# io_board.net
KiCad netlist of a schematic drawn in EAGLE
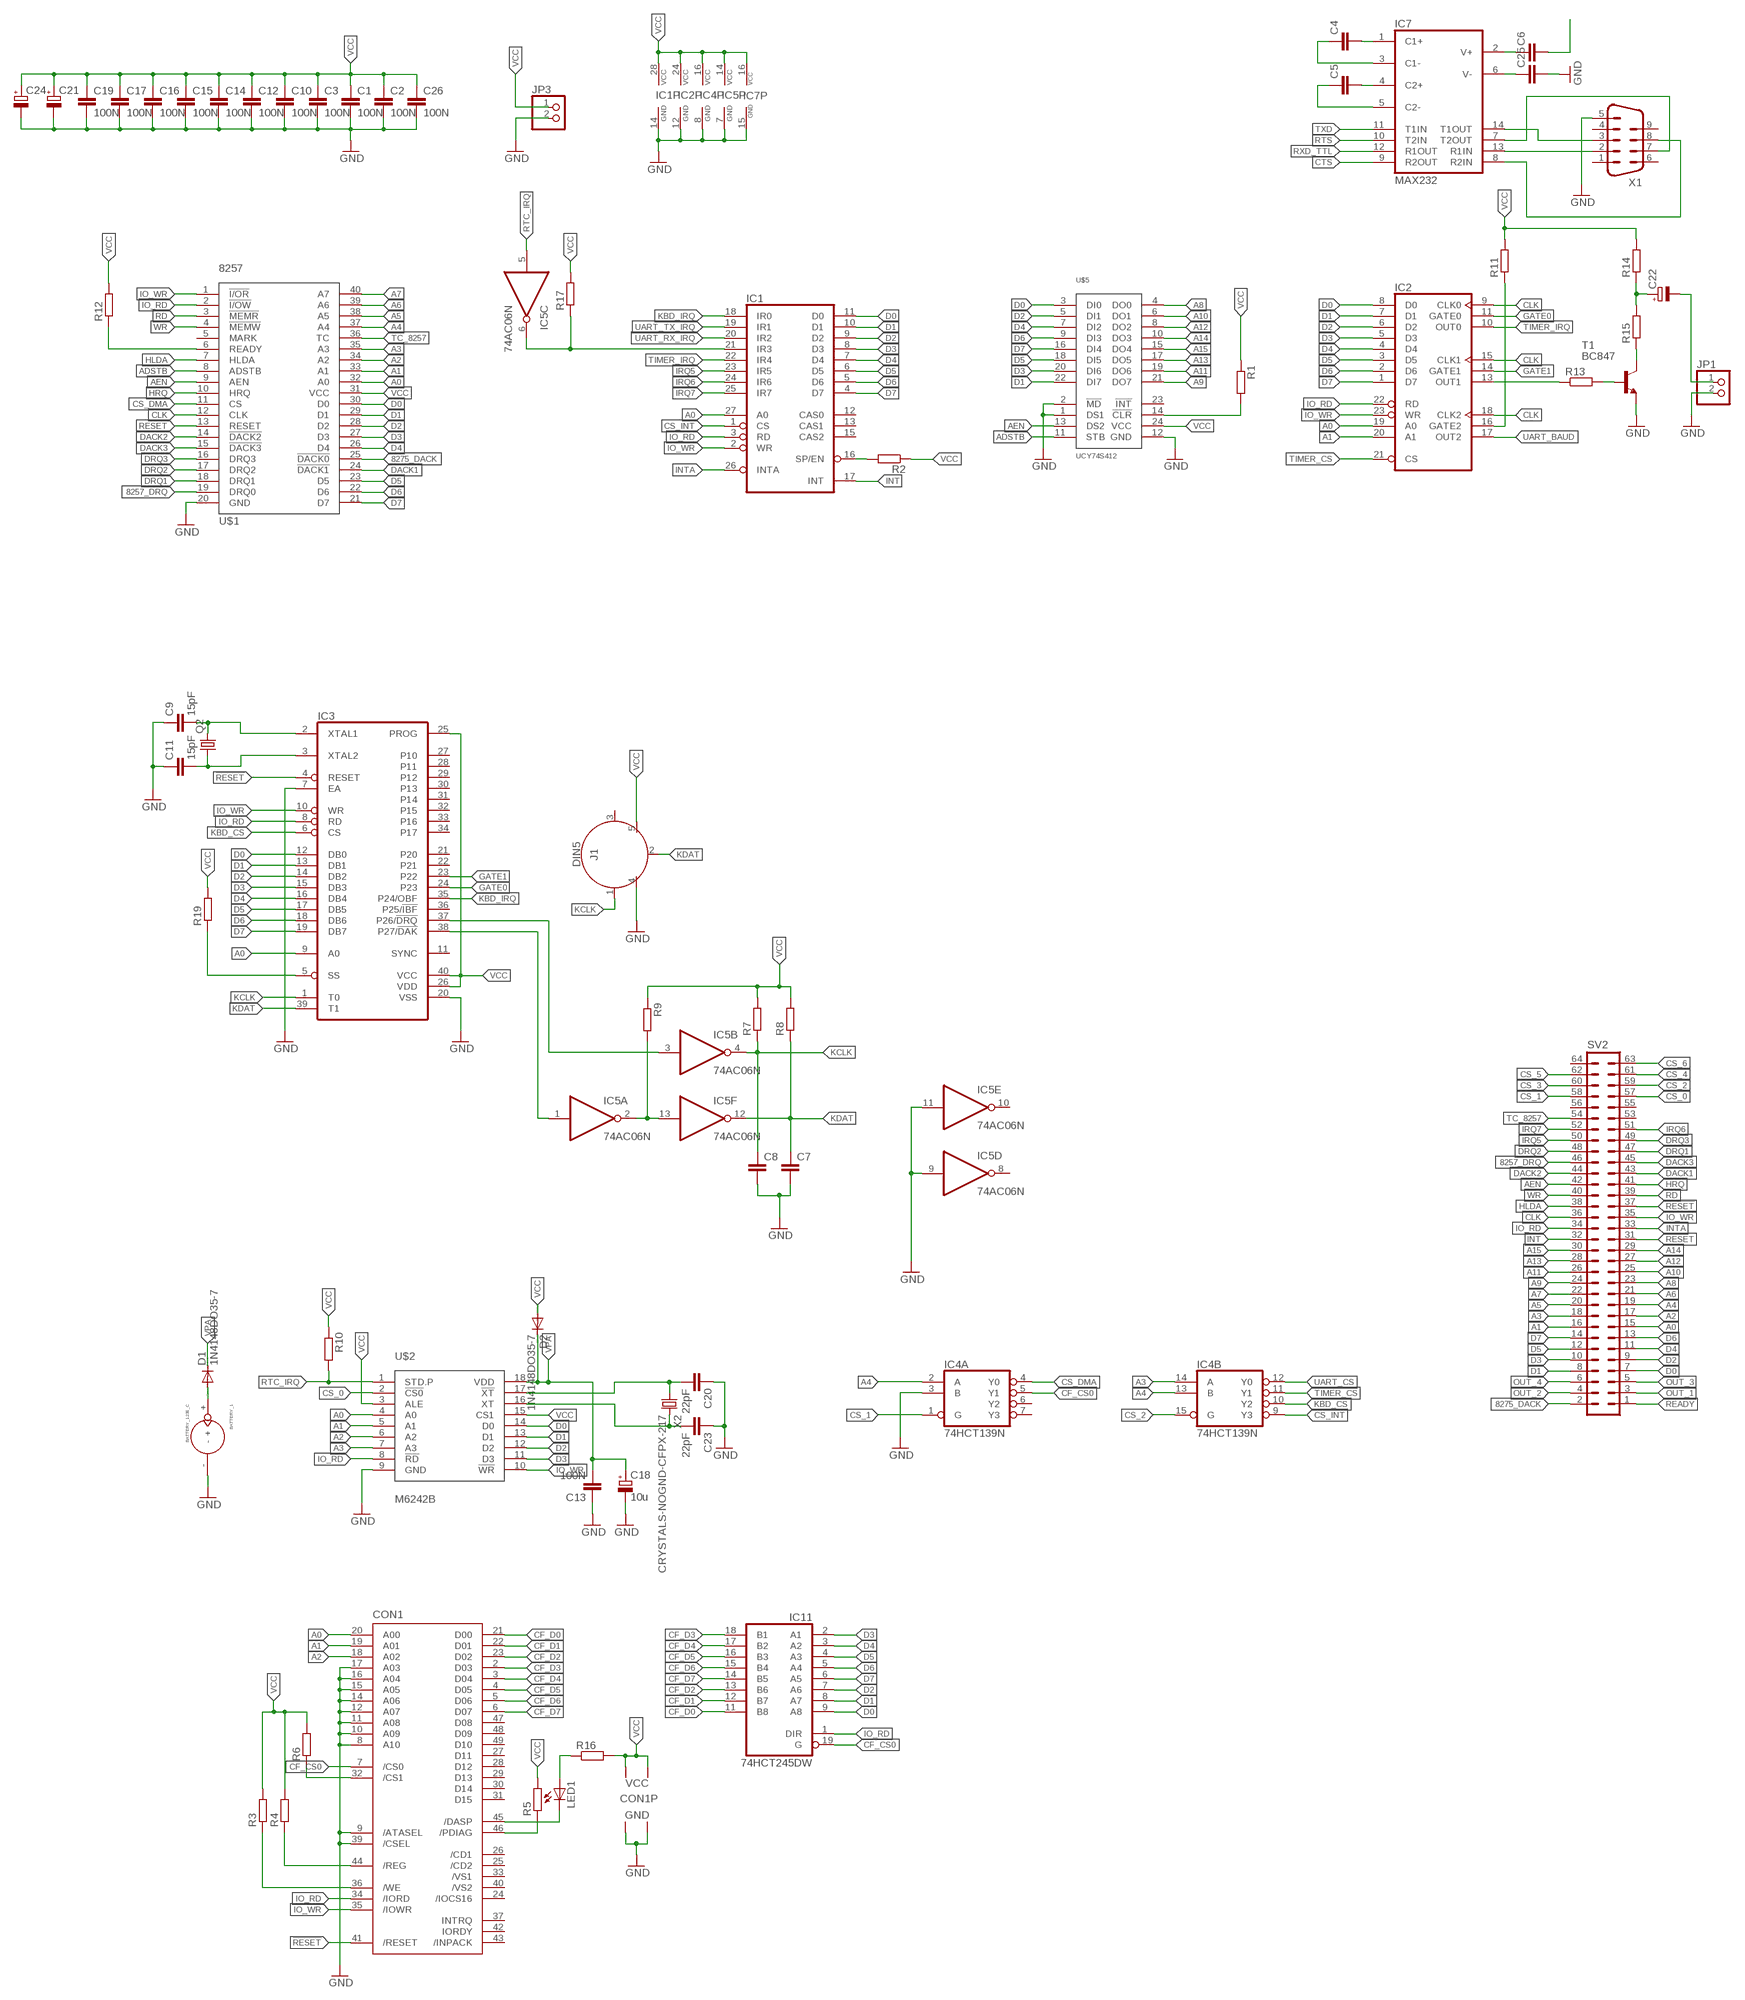
[diagram p0: schematic, sheet 1, part 1 of 2]
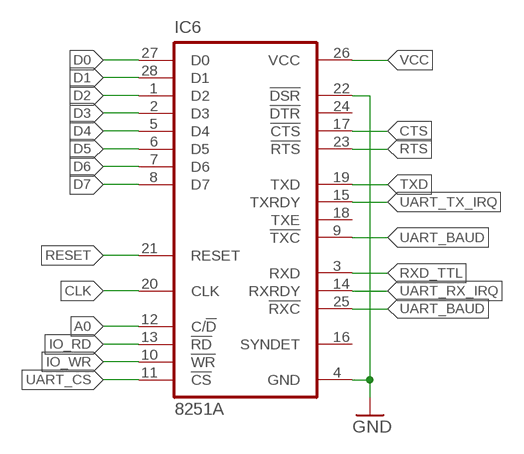
[diagram p1: schematic, sheet 1, part 2 of 2]

(export (version "E")
  (design (tool "Eeschema 10.0.6"))
  (components
    (comp (ref "BATTERY_1")
      (value "BATTERY_1236_C")
      (footprint "eagle-import:BATTERY_1236_C")
      (libsource (lib "eagle-import") (part "BATTERY_1236_C"))
    )
    (comp (ref "C1")
      (value "100N")
      (footprint "eagle-import:C0603")
      (libsource (lib "eagle-import") (part "C-EUC0603"))
    )
    (comp (ref "C2")
      (value "100N")
      (footprint "eagle-import:C1206")
      (libsource (lib "eagle-import") (part "C-EUC1206"))
    )
    (comp (ref "C3")
      (value "100N")
      (footprint "eagle-import:C0603")
      (libsource (lib "eagle-import") (part "C-EUC0603"))
    )
    (comp (ref "C4")
      (value "C-EUC0603")
      (footprint "eagle-import:C0603")
      (libsource (lib "eagle-import") (part "C-EUC0603"))
    )
    (comp (ref "C5")
      (value "C-EUC0603")
      (footprint "eagle-import:C0603")
      (libsource (lib "eagle-import") (part "C-EUC0603"))
    )
    (comp (ref "C6")
      (value "C-EUC0603")
      (footprint "eagle-import:C0603")
      (libsource (lib "eagle-import") (part "C-EUC0603"))
    )
    (comp (ref "C7")
      (value "C-EUC0603")
      (footprint "eagle-import:C0603")
      (libsource (lib "eagle-import") (part "C-EUC0603"))
    )
    (comp (ref "C8")
      (value "C-EUC0603")
      (footprint "eagle-import:C0603")
      (libsource (lib "eagle-import") (part "C-EUC0603"))
    )
    (comp (ref "C9")
      (value "15pF")
      (footprint "eagle-import:C0603")
      (libsource (lib "eagle-import") (part "C-EUC0603"))
    )
    (comp (ref "C10")
      (value "100N")
      (footprint "eagle-import:C0603")
      (libsource (lib "eagle-import") (part "C-EUC0603"))
    )
    (comp (ref "C11")
      (value "15pF")
      (footprint "eagle-import:C0603")
      (libsource (lib "eagle-import") (part "C-EUC0603"))
    )
    (comp (ref "C12")
      (value "100N")
      (footprint "eagle-import:C0603")
      (libsource (lib "eagle-import") (part "C-EUC0603"))
    )
    (comp (ref "C13")
      (value "100N")
      (footprint "eagle-import:C0603")
      (libsource (lib "eagle-import") (part "C-EUC0603"))
    )
    (comp (ref "C14")
      (value "100N")
      (footprint "eagle-import:C0603")
      (libsource (lib "eagle-import") (part "C-EUC0603"))
    )
    (comp (ref "C15")
      (value "100N")
      (footprint "eagle-import:C0603")
      (libsource (lib "eagle-import") (part "C-EUC0603"))
    )
    (comp (ref "C16")
      (value "100N")
      (footprint "eagle-import:C0603")
      (libsource (lib "eagle-import") (part "C-EUC0603"))
    )
    (comp (ref "C17")
      (value "100N")
      (footprint "eagle-import:C0603")
      (libsource (lib "eagle-import") (part "C-EUC0603"))
    )
    (comp (ref "C18")
      (value "10u")
      (footprint "eagle-import:SMC_B")
      (libsource (lib "eagle-import") (part "CPOL-EUSMCB"))
    )
    (comp (ref "C19")
      (value "100N")
      (footprint "eagle-import:C0603")
      (libsource (lib "eagle-import") (part "C-EUC0603"))
    )
    (comp (ref "C20")
      (value "22pF")
      (footprint "eagle-import:C0603")
      (libsource (lib "eagle-import") (part "C-EUC0603"))
    )
    (comp (ref "C21")
      (value "CPOL-EUE3.5-8")
      (footprint "eagle-import:E3,5-8")
      (libsource (lib "eagle-import") (part "CPOL-EUE3.5-8"))
    )
    (comp (ref "C22")
      (value "CPOL-EUE2-4")
      (footprint "eagle-import:E2-4")
      (libsource (lib "eagle-import") (part "CPOL-EUE2-4"))
    )
    (comp (ref "C23")
      (value "22pF")
      (footprint "eagle-import:C0603")
      (libsource (lib "eagle-import") (part "C-EUC0603"))
    )
    (comp (ref "C24")
      (value "CPOL-EUSMCB")
      (footprint "eagle-import:SMC_B")
      (libsource (lib "eagle-import") (part "CPOL-EUSMCB"))
    )
    (comp (ref "C25")
      (value "C-EUC0603")
      (footprint "eagle-import:C0603")
      (libsource (lib "eagle-import") (part "C-EUC0603"))
    )
    (comp (ref "C26")
      (value "100N")
      (footprint "eagle-import:C0603")
      (libsource (lib "eagle-import") (part "C-EUC0603"))
    )
    (comp (ref "CON1")
      (value "CF-CARD-IDE_MODE")
      (footprint "eagle-import:MI20-50PD-SF")
      (libsource (lib "eagle-import") (part "CF-CARD-IDE_MODE"))
    )
    (comp (ref "D1")
      (value "1N4148DO35-7")
      (footprint "eagle-import:DO35-7")
      (libsource (lib "eagle-import") (part "1N4148DO35-7"))
    )
    (comp (ref "D2")
      (value "1N4148DO35-7")
      (footprint "eagle-import:DO35-7")
      (libsource (lib "eagle-import") (part "1N4148DO35-7"))
    )
    (comp (ref "IC1")
      (value "8259A")
      (footprint "eagle-import:DIL28-6")
      (libsource (lib "eagle-import") (part "8259A"))
    )
    (comp (ref "IC2")
      (value "8253")
      (footprint "eagle-import:DIL24-6")
      (libsource (lib "eagle-import") (part "8253"))
    )
    (comp (ref "IC3")
      (value "UPI-8042AH")
      (footprint "eagle-import:DIL40")
      (libsource (lib "eagle-import") (part "UPI-8042AH"))
    )
    (comp (ref "IC4")
      (value "74HCT139N")
      (footprint "eagle-import:DIL16")
      (libsource (lib "eagle-import") (part "74139NHCT"))
    )
    (comp (ref "IC5")
      (value "74AC06N")
      (footprint "eagle-import:DIL14")
      (libsource (lib "eagle-import") (part "7406NAC"))
    )
    (comp (ref "IC6")
      (value "8251A")
      (footprint "eagle-import:DIL28-6")
      (libsource (lib "eagle-import") (part "8251A"))
    )
    (comp (ref "IC7")
      (value "MAX232")
      (footprint "eagle-import:DIL16")
      (fields (field (name "MF") "MAXIM") (field (name "MPN") "MAX232ACPE+"))
      (libsource (lib "eagle-import") (part "MAX232"))
    )
    (comp (ref "IC11")
      (value "74HCT245DW")
      (footprint "eagle-import:SO20W")
      (libsource (lib "eagle-import") (part "74245DWHCT"))
    )
    (comp (ref "J1")
      (value "DIN5")
      (footprint "eagle-import:DIN5-RA-PTH")
      (libsource (lib "eagle-import") (part "DIN5"))
    )
    (comp (ref "JP1")
      (value "PINHD-1X2")
      (footprint "eagle-import:1X02")
      (libsource (lib "eagle-import") (part "PINHD-1X2"))
    )
    (comp (ref "JP3")
      (value "PINHD-1X2/90")
      (footprint "eagle-import:1X02_90")
      (libsource (lib "eagle-import") (part "PINHD-1X2/90"))
    )
    (comp (ref "LED1")
      (value "LED5MM")
      (footprint "eagle-import:LED5MM")
      (libsource (lib "eagle-import") (part "LED5MM"))
    )
    (comp (ref "Q2")
      (value "CRYSTALHC49S")
      (footprint "eagle-import:HC49_S")
      (libsource (lib "eagle-import") (part "CRYSTALHC49S"))
    )
    (comp (ref "R1")
      (value "R-EU_R0603")
      (footprint "eagle-import:R0603")
      (libsource (lib "eagle-import") (part "R-EU_R0603"))
    )
    (comp (ref "R2")
      (value "R-EU_R0603")
      (footprint "eagle-import:R0603")
      (libsource (lib "eagle-import") (part "R-EU_R0603"))
    )
    (comp (ref "R3")
      (value "R-EU_R0603")
      (footprint "eagle-import:R0603")
      (libsource (lib "eagle-import") (part "R-EU_R0603"))
    )
    (comp (ref "R4")
      (value "R-EU_0204/7")
      (footprint "eagle-import:0204_7")
      (libsource (lib "eagle-import") (part "R-EU_0204/7"))
    )
    (comp (ref "R5")
      (value "R-EU_0207/10")
      (footprint "eagle-import:0207_10")
      (libsource (lib "eagle-import") (part "R-EU_0207/10"))
    )
    (comp (ref "R6")
      (value "R-EU_R0603")
      (footprint "eagle-import:R0603")
      (libsource (lib "eagle-import") (part "R-EU_R0603"))
    )
    (comp (ref "R7")
      (value "R-EU_0204/5")
      (footprint "eagle-import:0204_5")
      (libsource (lib "eagle-import") (part "R-EU_0204/5"))
    )
    (comp (ref "R8")
      (value "R-EU_M0805")
      (footprint "eagle-import:M0805")
      (libsource (lib "eagle-import") (part "R-EU_M0805"))
    )
    (comp (ref "R9")
      (value "R-EU_R0603")
      (footprint "eagle-import:R0603")
      (libsource (lib "eagle-import") (part "R-EU_R0603"))
    )
    (comp (ref "R10")
      (value "R-EU_R0603")
      (footprint "eagle-import:R0603")
      (libsource (lib "eagle-import") (part "R-EU_R0603"))
    )
    (comp (ref "R11")
      (value "R-EU_R0603")
      (footprint "eagle-import:R0603")
      (libsource (lib "eagle-import") (part "R-EU_R0603"))
    )
    (comp (ref "R12")
      (value "R-EU_R0603")
      (footprint "eagle-import:R0603")
      (libsource (lib "eagle-import") (part "R-EU_R0603"))
    )
    (comp (ref "R13")
      (value "R-EU_R0603")
      (footprint "eagle-import:R0603")
      (libsource (lib "eagle-import") (part "R-EU_R0603"))
    )
    (comp (ref "R14")
      (value "R-EU_0204/5")
      (footprint "eagle-import:0204_5")
      (libsource (lib "eagle-import") (part "R-EU_0204/5"))
    )
    (comp (ref "R15")
      (value "R-EU_R0603")
      (footprint "eagle-import:R0603")
      (libsource (lib "eagle-import") (part "R-EU_R0603"))
    )
    (comp (ref "R16")
      (value "R-EU_R0603")
      (footprint "eagle-import:R0603")
      (libsource (lib "eagle-import") (part "R-EU_R0603"))
    )
    (comp (ref "R17")
      (value "R-EU_0204/7")
      (footprint "eagle-import:0204_7")
      (libsource (lib "eagle-import") (part "R-EU_0204/7"))
    )
    (comp (ref "R19")
      (value "R-EU_0204/5")
      (footprint "eagle-import:0204_5")
      (libsource (lib "eagle-import") (part "R-EU_0204/5"))
    )
    (comp (ref "SV2")
      (value "ML64L")
      (footprint "eagle-import:ML64L")
      (libsource (lib "eagle-import") (part "ML64L"))
    )
    (comp (ref "T1")
      (value "BC847")
      (footprint "eagle-import:SOT23")
      (libsource (lib "eagle-import") (part "BC847"))
    )
    (comp (ref "U$1")
      (value "8257")
      (footprint "eagle-import:DIL40")
      (libsource (lib "eagle-import") (part "8257"))
    )
    (comp (ref "U$2")
      (value "M6242B")
      (footprint "eagle-import:DIL18")
      (libsource (lib "eagle-import") (part "M6242B"))
    )
    (comp (ref "U$5")
      (value "UCY74S412")
      (footprint "eagle-import:DIL24-6")
      (libsource (lib "eagle-import") (part "UCY74S412"))
    )
    (comp (ref "X1")
      (value "M09HP")
      (footprint "eagle-import:M09HP")
      (libsource (lib "eagle-import") (part "M09HP"))
    )
    (comp (ref "X2")
      (value "CRYSTALS-NOGND-CFPX-217")
      (footprint "eagle-import:3.2X1.5-2-PAD")
      (libsource (lib "eagle-import") (part "CRYSTALS-NOGND-CFPX-217"))
    )
  )
  (nets
    (net (code "1") (name "/~{RESET}") (class "Default")
      (node (ref "CON1") (pin "41") (pinfunction "/RESET_41") (pintype "input"))
      (node (ref "IC3") (pin "4") (pinfunction "RESET_4") (pintype "input"))
      (node (ref "SV2") (pin "37") (pinfunction "37_37") (pintype "passive"))
    )
    (net (code "2") (name "8257_DRQ") (class "Default")
      (node (ref "SV2") (pin "46") (pinfunction "46_46") (pintype "passive"))
      (node (ref "U$1") (pin "19") (pinfunction "DRQ0_19") (pintype "bidirectional"))
    )
    (net (code "3") (name "8275_DACK") (class "Default")
      (node (ref "SV2") (pin "2") (pinfunction "2_2") (pintype "passive"))
      (node (ref "U$1") (pin "25") (pinfunction "~{DACK0}_25") (pintype "bidirectional"))
    )
    (net (code "4") (name "A0") (class "Default")
      (node (ref "CON1") (pin "20") (pinfunction "A00_20") (pintype "input"))
      (node (ref "IC1") (pin "27") (pinfunction "A0_27") (pintype "input"))
      (node (ref "IC2") (pin "19") (pinfunction "A0_19") (pintype "input"))
      (node (ref "IC3") (pin "9") (pinfunction "A0_9") (pintype "input"))
      (node (ref "IC6") (pin "12") (pinfunction "C/~{D}_12") (pintype "input"))
      (node (ref "SV2") (pin "15") (pinfunction "15_15") (pintype "passive"))
      (node (ref "U$1") (pin "32") (pinfunction "A0_32") (pintype "bidirectional"))
      (node (ref "U$2") (pin "4") (pinfunction "A0_4") (pintype "bidirectional"))
    )
    (net (code "5") (name "A1") (class "Default")
      (node (ref "CON1") (pin "19") (pinfunction "A01_19") (pintype "input"))
      (node (ref "IC2") (pin "20") (pinfunction "A1_20") (pintype "input"))
      (node (ref "SV2") (pin "16") (pinfunction "16_16") (pintype "passive"))
      (node (ref "U$1") (pin "33") (pinfunction "A1_33") (pintype "bidirectional"))
      (node (ref "U$2") (pin "5") (pinfunction "A1_5") (pintype "bidirectional"))
    )
    (net (code "6") (name "A2") (class "Default")
      (node (ref "CON1") (pin "18") (pinfunction "A02_18") (pintype "input"))
      (node (ref "SV2") (pin "17") (pinfunction "17_17") (pintype "passive"))
      (node (ref "U$1") (pin "34") (pinfunction "A2_34") (pintype "bidirectional"))
      (node (ref "U$2") (pin "6") (pinfunction "A2_6") (pintype "bidirectional"))
    )
    (net (code "7") (name "A3") (class "Default")
      (node (ref "IC4") (pin "14") (pinfunction "A_14") (pintype "input"))
      (node (ref "SV2") (pin "18") (pinfunction "18_18") (pintype "passive"))
      (node (ref "U$1") (pin "35") (pinfunction "A3_35") (pintype "bidirectional"))
      (node (ref "U$2") (pin "7") (pinfunction "A3_7") (pintype "bidirectional"))
    )
    (net (code "8") (name "A4") (class "Default")
      (node (ref "IC4") (pin "13") (pinfunction "B_13") (pintype "input"))
      (node (ref "IC4") (pin "2") (pinfunction "A_2") (pintype "input"))
      (node (ref "SV2") (pin "19") (pinfunction "19_19") (pintype "passive"))
      (node (ref "U$1") (pin "37") (pinfunction "A4_37") (pintype "bidirectional"))
    )
    (net (code "9") (name "A5") (class "Default")
      (node (ref "SV2") (pin "20") (pinfunction "20_20") (pintype "passive"))
      (node (ref "U$1") (pin "38") (pinfunction "A5_38") (pintype "bidirectional"))
    )
    (net (code "10") (name "A6") (class "Default")
      (node (ref "SV2") (pin "21") (pinfunction "21_21") (pintype "passive"))
      (node (ref "U$1") (pin "39") (pinfunction "A6_39") (pintype "bidirectional"))
    )
    (net (code "11") (name "A7") (class "Default")
      (node (ref "SV2") (pin "22") (pinfunction "22_22") (pintype "passive"))
      (node (ref "U$1") (pin "40") (pinfunction "A7_40") (pintype "bidirectional"))
    )
    (net (code "12") (name "A8") (class "Default")
      (node (ref "SV2") (pin "23") (pinfunction "23_23") (pintype "passive"))
      (node (ref "U$5") (pin "4") (pinfunction "DO0_4") (pintype "bidirectional"))
    )
    (net (code "13") (name "A9") (class "Default")
      (node (ref "SV2") (pin "24") (pinfunction "24_24") (pintype "passive"))
      (node (ref "U$5") (pin "21") (pinfunction "DO7_21") (pintype "bidirectional"))
    )
    (net (code "14") (name "A10") (class "Default")
      (node (ref "SV2") (pin "25") (pinfunction "25_25") (pintype "passive"))
      (node (ref "U$5") (pin "6") (pinfunction "DO1_6") (pintype "bidirectional"))
    )
    (net (code "15") (name "A11") (class "Default")
      (node (ref "SV2") (pin "26") (pinfunction "26_26") (pintype "passive"))
      (node (ref "U$5") (pin "19") (pinfunction "DO6_19") (pintype "bidirectional"))
    )
    (net (code "16") (name "A12") (class "Default")
      (node (ref "SV2") (pin "27") (pinfunction "27_27") (pintype "passive"))
      (node (ref "U$5") (pin "8") (pinfunction "DO2_8") (pintype "bidirectional"))
    )
    (net (code "17") (name "A13") (class "Default")
      (node (ref "SV2") (pin "28") (pinfunction "28_28") (pintype "passive"))
      (node (ref "U$5") (pin "17") (pinfunction "DO5_17") (pintype "bidirectional"))
    )
    (net (code "18") (name "A14") (class "Default")
      (node (ref "SV2") (pin "29") (pinfunction "29_29") (pintype "passive"))
      (node (ref "U$5") (pin "10") (pinfunction "DO3_10") (pintype "bidirectional"))
    )
    (net (code "19") (name "A15") (class "Default")
      (node (ref "SV2") (pin "30") (pinfunction "30_30") (pintype "passive"))
      (node (ref "U$5") (pin "15") (pinfunction "DO4_15") (pintype "bidirectional"))
    )
    (net (code "20") (name "ADSTB") (class "Default")
      (node (ref "U$1") (pin "8") (pinfunction "ADSTB_8") (pintype "bidirectional"))
      (node (ref "U$5") (pin "11") (pinfunction "STB_11") (pintype "bidirectional"))
    )
    (net (code "21") (name "AEN") (class "Default")
      (node (ref "SV2") (pin "42") (pinfunction "42_42") (pintype "passive"))
      (node (ref "U$1") (pin "9") (pinfunction "AEN_9") (pintype "bidirectional"))
      (node (ref "U$5") (pin "13") (pinfunction "DS2_13") (pintype "bidirectional"))
    )
    (net (code "22") (name "CF_CS0") (class "Default")
      (node (ref "CON1") (pin "7") (pinfunction "/CS0_7") (pintype "input"))
      (node (ref "IC11") (pin "19") (pinfunction "G_19") (pintype "input"))
      (node (ref "IC4") (pin "5") (pinfunction "Y1_5") (pintype "output"))
    )
    (net (code "23") (name "CF_D0") (class "Default")
      (node (ref "CON1") (pin "21") (pinfunction "D00_21") (pintype "bidirectional"))
      (node (ref "IC11") (pin "11") (pinfunction "B8_11") (pintype "bidirectional"))
    )
    (net (code "24") (name "CF_D1") (class "Default")
      (node (ref "CON1") (pin "22") (pinfunction "D01_22") (pintype "bidirectional"))
      (node (ref "IC11") (pin "12") (pinfunction "B7_12") (pintype "bidirectional"))
    )
    (net (code "25") (name "CF_D2") (class "Default")
      (node (ref "CON1") (pin "23") (pinfunction "D02_23") (pintype "bidirectional"))
      (node (ref "IC11") (pin "13") (pinfunction "B6_13") (pintype "bidirectional"))
    )
    (net (code "26") (name "CF_D3") (class "Default")
      (node (ref "CON1") (pin "2") (pinfunction "D03_2") (pintype "bidirectional"))
      (node (ref "IC11") (pin "18") (pinfunction "B1_18") (pintype "bidirectional"))
    )
    (net (code "27") (name "CF_D4") (class "Default")
      (node (ref "CON1") (pin "3") (pinfunction "D04_3") (pintype "bidirectional"))
      (node (ref "IC11") (pin "17") (pinfunction "B2_17") (pintype "bidirectional"))
    )
    (net (code "28") (name "CF_D5") (class "Default")
      (node (ref "CON1") (pin "4") (pinfunction "D05_4") (pintype "bidirectional"))
      (node (ref "IC11") (pin "16") (pinfunction "B3_16") (pintype "bidirectional"))
    )
    (net (code "29") (name "CF_D6") (class "Default")
      (node (ref "CON1") (pin "5") (pinfunction "D06_5") (pintype "bidirectional"))
      (node (ref "IC11") (pin "15") (pinfunction "B4_15") (pintype "bidirectional"))
    )
    (net (code "30") (name "CF_D7") (class "Default")
      (node (ref "CON1") (pin "6") (pinfunction "D07_6") (pintype "bidirectional"))
      (node (ref "IC11") (pin "14") (pinfunction "B5_14") (pintype "bidirectional"))
    )
    (net (code "31") (name "CLK") (class "Default")
      (node (ref "IC2") (pin "15") (pinfunction "CLK1_15") (pintype "input"))
      (node (ref "IC2") (pin "18") (pinfunction "CLK2_18") (pintype "input"))
      (node (ref "IC2") (pin "9") (pinfunction "CLK0_9") (pintype "input"))
      (node (ref "IC6") (pin "20") (pinfunction "CLK_20") (pintype "input"))
      (node (ref "SV2") (pin "36") (pinfunction "36_36") (pintype "passive"))
      (node (ref "U$1") (pin "12") (pinfunction "CLK_12") (pintype "bidirectional"))
    )
    (net (code "32") (name "CS_0") (class "Default")
      (node (ref "SV2") (pin "57") (pinfunction "57_57") (pintype "passive"))
      (node (ref "U$2") (pin "2") (pinfunction "~{CS0}_2") (pintype "bidirectional"))
    )
    (net (code "33") (name "CS_1") (class "Default")
      (node (ref "IC4") (pin "1") (pinfunction "G_1") (pintype "input"))
      (node (ref "SV2") (pin "58") (pinfunction "58_58") (pintype "passive"))
    )
    (net (code "34") (name "CS_2") (class "Default")
      (node (ref "IC4") (pin "15") (pinfunction "G_15") (pintype "input"))
      (node (ref "SV2") (pin "59") (pinfunction "59_59") (pintype "passive"))
    )
    (net (code "35") (name "CS_3") (class "Default")
      (node (ref "SV2") (pin "60") (pinfunction "60_60") (pintype "passive"))
    )
    (net (code "36") (name "CS_4") (class "Default")
      (node (ref "SV2") (pin "61") (pinfunction "61_61") (pintype "passive"))
    )
    (net (code "37") (name "CS_5") (class "Default")
      (node (ref "SV2") (pin "62") (pinfunction "62_62") (pintype "passive"))
    )
    (net (code "38") (name "CS_6") (class "Default")
      (node (ref "SV2") (pin "63") (pinfunction "63_63") (pintype "passive"))
    )
    (net (code "39") (name "CS_DMA") (class "Default")
      (node (ref "IC4") (pin "4") (pinfunction "Y0_4") (pintype "output"))
      (node (ref "U$1") (pin "11") (pinfunction "CS_11") (pintype "bidirectional"))
    )
    (net (code "40") (name "CS_INT") (class "Default")
      (node (ref "IC1") (pin "1") (pinfunction "CS_1") (pintype "input"))
      (node (ref "IC4") (pin "9") (pinfunction "Y3_9") (pintype "output"))
    )
    (net (code "41") (name "CTS") (class "Default")
      (node (ref "IC6") (pin "17") (pinfunction "~{CTS}_17") (pintype "input"))
      (node (ref "IC7") (pin "9") (pinfunction "R2OUT_9") (pintype "output"))
    )
    (net (code "42") (name "D0") (class "Default")
      (node (ref "IC1") (pin "11") (pinfunction "D0_11") (pintype "bidirectional"))
      (node (ref "IC11") (pin "9") (pinfunction "A8_9") (pintype "bidirectional"))
      (node (ref "IC2") (pin "8") (pinfunction "D0_8") (pintype "bidirectional"))
      (node (ref "IC3") (pin "12") (pinfunction "DB0_12") (pintype "bidirectional"))
      (node (ref "IC6") (pin "27") (pinfunction "D0_27") (pintype "tri_state"))
      (node (ref "SV2") (pin "7") (pinfunction "7_7") (pintype "passive"))
      (node (ref "U$1") (pin "30") (pinfunction "D0_30") (pintype "bidirectional"))
      (node (ref "U$2") (pin "14") (pinfunction "D0_14") (pintype "bidirectional"))
      (node (ref "U$5") (pin "3") (pinfunction "DI0_3") (pintype "bidirectional"))
    )
    (net (code "43") (name "D1") (class "Default")
      (node (ref "IC1") (pin "10") (pinfunction "D1_10") (pintype "bidirectional"))
      (node (ref "IC11") (pin "8") (pinfunction "A7_8") (pintype "bidirectional"))
      (node (ref "IC2") (pin "7") (pinfunction "D1_7") (pintype "bidirectional"))
      (node (ref "IC3") (pin "13") (pinfunction "DB1_13") (pintype "bidirectional"))
      (node (ref "IC6") (pin "28") (pinfunction "D1_28") (pintype "tri_state"))
      (node (ref "SV2") (pin "8") (pinfunction "8_8") (pintype "passive"))
      (node (ref "U$1") (pin "29") (pinfunction "D1_29") (pintype "bidirectional"))
      (node (ref "U$2") (pin "13") (pinfunction "D1_13") (pintype "bidirectional"))
      (node (ref "U$5") (pin "22") (pinfunction "DI7_22") (pintype "bidirectional"))
    )
    (net (code "44") (name "D2") (class "Default")
      (node (ref "IC1") (pin "9") (pinfunction "D2_9") (pintype "bidirectional"))
      (node (ref "IC11") (pin "7") (pinfunction "A6_7") (pintype "bidirectional"))
      (node (ref "IC2") (pin "6") (pinfunction "D2_6") (pintype "bidirectional"))
      (node (ref "IC3") (pin "14") (pinfunction "DB2_14") (pintype "bidirectional"))
      (node (ref "IC6") (pin "1") (pinfunction "D2_1") (pintype "tri_state"))
      (node (ref "SV2") (pin "9") (pinfunction "9_9") (pintype "passive"))
      (node (ref "U$1") (pin "28") (pinfunction "D2_28") (pintype "bidirectional"))
      (node (ref "U$2") (pin "12") (pinfunction "D2_12") (pintype "bidirectional"))
      (node (ref "U$5") (pin "5") (pinfunction "DI1_5") (pintype "bidirectional"))
    )
    (net (code "45") (name "D3") (class "Default")
      (node (ref "IC1") (pin "8") (pinfunction "D3_8") (pintype "bidirectional"))
      (node (ref "IC11") (pin "2") (pinfunction "A1_2") (pintype "bidirectional"))
      (node (ref "IC2") (pin "5") (pinfunction "D3_5") (pintype "bidirectional"))
      (node (ref "IC3") (pin "15") (pinfunction "DB3_15") (pintype "bidirectional"))
      (node (ref "IC6") (pin "2") (pinfunction "D3_2") (pintype "tri_state"))
      (node (ref "SV2") (pin "10") (pinfunction "10_10") (pintype "passive"))
      (node (ref "U$1") (pin "27") (pinfunction "D3_27") (pintype "bidirectional"))
      (node (ref "U$2") (pin "11") (pinfunction "D3_11") (pintype "bidirectional"))
      (node (ref "U$5") (pin "20") (pinfunction "DI6_20") (pintype "bidirectional"))
    )
    (net (code "46") (name "D4") (class "Default")
      (node (ref "IC1") (pin "7") (pinfunction "D4_7") (pintype "bidirectional"))
      (node (ref "IC11") (pin "3") (pinfunction "A2_3") (pintype "bidirectional"))
      (node (ref "IC2") (pin "4") (pinfunction "D4_4") (pintype "bidirectional"))
      (node (ref "IC3") (pin "16") (pinfunction "DB4_16") (pintype "bidirectional"))
      (node (ref "IC6") (pin "5") (pinfunction "D4_5") (pintype "tri_state"))
      (node (ref "SV2") (pin "11") (pinfunction "11_11") (pintype "passive"))
      (node (ref "U$1") (pin "26") (pinfunction "D4_26") (pintype "bidirectional"))
      (node (ref "U$5") (pin "7") (pinfunction "DI2_7") (pintype "bidirectional"))
    )
    (net (code "47") (name "D5") (class "Default")
      (node (ref "IC1") (pin "6") (pinfunction "D5_6") (pintype "bidirectional"))
      (node (ref "IC11") (pin "4") (pinfunction "A3_4") (pintype "bidirectional"))
      (node (ref "IC2") (pin "3") (pinfunction "D5_3") (pintype "bidirectional"))
      (node (ref "IC3") (pin "17") (pinfunction "DB5_17") (pintype "bidirectional"))
      (node (ref "IC6") (pin "6") (pinfunction "D5_6") (pintype "tri_state"))
      (node (ref "SV2") (pin "12") (pinfunction "12_12") (pintype "passive"))
      (node (ref "U$1") (pin "23") (pinfunction "D5_23") (pintype "bidirectional"))
      (node (ref "U$5") (pin "18") (pinfunction "DI5_18") (pintype "bidirectional"))
    )
    (net (code "48") (name "D6") (class "Default")
      (node (ref "IC1") (pin "5") (pinfunction "D6_5") (pintype "bidirectional"))
      (node (ref "IC11") (pin "5") (pinfunction "A4_5") (pintype "bidirectional"))
      (node (ref "IC2") (pin "2") (pinfunction "D6_2") (pintype "bidirectional"))
      (node (ref "IC3") (pin "18") (pinfunction "DB6_18") (pintype "bidirectional"))
      (node (ref "IC6") (pin "7") (pinfunction "D6_7") (pintype "tri_state"))
      (node (ref "SV2") (pin "13") (pinfunction "13_13") (pintype "passive"))
      (node (ref "U$1") (pin "22") (pinfunction "D6_22") (pintype "bidirectional"))
      (node (ref "U$5") (pin "9") (pinfunction "DI3_9") (pintype "bidirectional"))
    )
    (net (code "49") (name "D7") (class "Default")
      (node (ref "IC1") (pin "4") (pinfunction "D7_4") (pintype "bidirectional"))
      (node (ref "IC11") (pin "6") (pinfunction "A5_6") (pintype "bidirectional"))
      (node (ref "IC2") (pin "1") (pinfunction "D7_1") (pintype "bidirectional"))
      (node (ref "IC3") (pin "19") (pinfunction "DB7_19") (pintype "bidirectional"))
      (node (ref "IC6") (pin "8") (pinfunction "D7_8") (pintype "tri_state"))
      (node (ref "SV2") (pin "14") (pinfunction "14_14") (pintype "passive"))
      (node (ref "U$1") (pin "21") (pinfunction "D7_21") (pintype "bidirectional"))
      (node (ref "U$5") (pin "16") (pinfunction "DI4_16") (pintype "bidirectional"))
    )
    (net (code "50") (name "DACK1") (class "Default")
      (node (ref "SV2") (pin "43") (pinfunction "43_43") (pintype "passive"))
      (node (ref "U$1") (pin "24") (pinfunction "~{DACK1}_24") (pintype "bidirectional"))
    )
    (net (code "51") (name "DACK2") (class "Default")
      (node (ref "SV2") (pin "44") (pinfunction "44_44") (pintype "passive"))
      (node (ref "U$1") (pin "14") (pinfunction "~{DACK2}_14") (pintype "bidirectional"))
    )
    (net (code "52") (name "DACK3") (class "Default")
      (node (ref "SV2") (pin "45") (pinfunction "45_45") (pintype "passive"))
      (node (ref "U$1") (pin "15") (pinfunction "~{DACK3}_15") (pintype "bidirectional"))
    )
    (net (code "53") (name "DRQ1") (class "Default")
      (node (ref "SV2") (pin "47") (pinfunction "47_47") (pintype "passive"))
      (node (ref "U$1") (pin "18") (pinfunction "DRQ1_18") (pintype "bidirectional"))
    )
    (net (code "54") (name "DRQ2") (class "Default")
      (node (ref "SV2") (pin "48") (pinfunction "48_48") (pintype "passive"))
      (node (ref "U$1") (pin "17") (pinfunction "DRQ2_17") (pintype "bidirectional"))
    )
    (net (code "55") (name "DRQ3") (class "Default")
      (node (ref "SV2") (pin "49") (pinfunction "49_49") (pintype "passive"))
      (node (ref "U$1") (pin "16") (pinfunction "DRQ3_16") (pintype "bidirectional"))
    )
    (net (code "56") (name "GATE0") (class "Default")
      (node (ref "IC2") (pin "11") (pinfunction "GATE0_11") (pintype "input"))
      (node (ref "IC3") (pin "24") (pinfunction "P23_24") (pintype "bidirectional"))
    )
    (net (code "57") (name "GATE1") (class "Default")
      (node (ref "IC2") (pin "14") (pinfunction "GATE1_14") (pintype "input"))
      (node (ref "IC3") (pin "23") (pinfunction "P22_23") (pintype "bidirectional"))
    )
    (net (code "58") (name "GND") (class "Default")
      (node (ref "BATTERY_1") (pin "-") (pinfunction "-_-") (pintype "bidirectional"))
      (node (ref "C1") (pin "2") (pinfunction "2_2") (pintype "passive"))
      (node (ref "C10") (pin "2") (pinfunction "2_2") (pintype "passive"))
      (node (ref "C11") (pin "1") (pinfunction "1_1") (pintype "passive"))
      (node (ref "C12") (pin "2") (pinfunction "2_2") (pintype "passive"))
      (node (ref "C13") (pin "1") (pinfunction "1_1") (pintype "passive"))
      (node (ref "C14") (pin "2") (pinfunction "2_2") (pintype "passive"))
      (node (ref "C15") (pin "2") (pinfunction "2_2") (pintype "passive"))
      (node (ref "C16") (pin "2") (pinfunction "2_2") (pintype "passive"))
      (node (ref "C17") (pin "2") (pinfunction "2_2") (pintype "passive"))
      (node (ref "C18") (pin "-") (pinfunction "-_-") (pintype "passive"))
      (node (ref "C19") (pin "2") (pinfunction "2_2") (pintype "passive"))
      (node (ref "C2") (pin "2") (pinfunction "2_2") (pintype "passive"))
      (node (ref "C20") (pin "1") (pinfunction "1_1") (pintype "passive"))
      (node (ref "C21") (pin "-") (pinfunction "-_-") (pintype "passive"))
      (node (ref "C23") (pin "1") (pinfunction "1_1") (pintype "passive"))
      (node (ref "C24") (pin "-") (pinfunction "-_-") (pintype "passive"))
      (node (ref "C25") (pin "2") (pinfunction "2_2") (pintype "passive"))
      (node (ref "C26") (pin "2") (pinfunction "2_2") (pintype "passive"))
      (node (ref "C3") (pin "2") (pinfunction "2_2") (pintype "passive"))
      (node (ref "C7") (pin "2") (pinfunction "2_2") (pintype "passive"))
      (node (ref "C8") (pin "2") (pinfunction "2_2") (pintype "passive"))
      (node (ref "C9") (pin "1") (pinfunction "1_1") (pintype "passive"))
      (node (ref "CON1") (pin "1") (pinfunction "GND1_1") (pintype "power_in"))
      (node (ref "CON1") (pin "10") (pinfunction "A09_10") (pintype "input"))
      (node (ref "CON1") (pin "11") (pinfunction "A08_11") (pintype "input"))
      (node (ref "CON1") (pin "12") (pinfunction "A07_12") (pintype "input"))
      (node (ref "CON1") (pin "14") (pinfunction "A06_14") (pintype "input"))
      (node (ref "CON1") (pin "15") (pinfunction "A05_15") (pintype "input"))
      (node (ref "CON1") (pin "16") (pinfunction "A04_16") (pintype "input"))
      (node (ref "CON1") (pin "17") (pinfunction "A03_17") (pintype "input"))
      (node (ref "CON1") (pin "39") (pinfunction "/CSEL_39") (pintype "input"))
      (node (ref "CON1") (pin "50") (pinfunction "GND2_50") (pintype "power_in"))
      (node (ref "CON1") (pin "8") (pinfunction "A10_8") (pintype "input"))
      (node (ref "CON1") (pin "9") (pinfunction "/ATASEL_9") (pintype "input"))
      (node (ref "IC1") (pin "14") (pinfunction "GND_14") (pintype "power_in"))
      (node (ref "IC2") (pin "12") (pinfunction "GND_12") (pintype "power_in"))
      (node (ref "IC3") (pin "20") (pinfunction "VSS_20") (pintype "power_in"))
      (node (ref "IC3") (pin "7") (pinfunction "EA_7") (pintype "input"))
      (node (ref "IC4") (pin "3") (pinfunction "B_3") (pintype "input"))
      (node (ref "IC4") (pin "8") (pinfunction "GND_8") (pintype "power_in"))
      (node (ref "IC5") (pin "11") (pinfunction "I_11") (pintype "input"))
      (node (ref "IC5") (pin "7") (pinfunction "GND_7") (pintype "power_in"))
      (node (ref "IC5") (pin "9") (pinfunction "I_9") (pintype "input"))
      (node (ref "IC6") (pin "22") (pinfunction "~{DSR}_22") (pintype "input"))
      (node (ref "IC6") (pin "4") (pinfunction "GND_4") (pintype "power_in"))
      (node (ref "IC7") (pin "15") (pinfunction "GND_15") (pintype "power_in"))
      (node (ref "J1") (pin "4") (pinfunction "4_4") (pintype "bidirectional"))
      (node (ref "JP1") (pin "2") (pinfunction "2_2") (pintype "passive"))
      (node (ref "JP3") (pin "2") (pinfunction "2_2") (pintype "passive"))
      (node (ref "T1") (pin "2") (pinfunction "E_2") (pintype "passive"))
      (node (ref "U$1") (pin "20") (pinfunction "GND_20") (pintype "bidirectional"))
      (node (ref "U$2") (pin "9") (pinfunction "GND_9") (pintype "bidirectional"))
      (node (ref "U$5") (pin "1") (pinfunction "DS1_1") (pintype "bidirectional"))
      (node (ref "U$5") (pin "12") (pinfunction "GND_12") (pintype "bidirectional"))
      (node (ref "U$5") (pin "2") (pinfunction "~{MD}_2") (pintype "bidirectional"))
      (node (ref "X1") (pin "5") (pinfunction "5_5") (pintype "passive"))
    )
    (net (code "59") (name "HLDA") (class "Default")
      (node (ref "SV2") (pin "38") (pinfunction "38_38") (pintype "passive"))
      (node (ref "U$1") (pin "7") (pinfunction "HLDA_7") (pintype "bidirectional"))
    )
    (net (code "60") (name "HRQ") (class "Default")
      (node (ref "SV2") (pin "41") (pinfunction "41_41") (pintype "passive"))
      (node (ref "U$1") (pin "10") (pinfunction "HRQ_10") (pintype "bidirectional"))
    )
    (net (code "61") (name "INT") (class "Default")
      (node (ref "IC1") (pin "17") (pinfunction "INT_17") (pintype "output"))
      (node (ref "SV2") (pin "32") (pinfunction "32_32") (pintype "passive"))
    )
    (net (code "62") (name "INTA") (class "Default")
      (node (ref "IC1") (pin "26") (pinfunction "INTA_26") (pintype "input"))
      (node (ref "SV2") (pin "33") (pinfunction "33_33") (pintype "passive"))
    )
    (net (code "63") (name "IO_RD") (class "Default")
      (node (ref "CON1") (pin "34") (pinfunction "/IORD_34") (pintype "input"))
      (node (ref "IC1") (pin "3") (pinfunction "RD_3") (pintype "input"))
      (node (ref "IC11") (pin "1") (pinfunction "DIR_1") (pintype "input"))
      (node (ref "IC2") (pin "22") (pinfunction "RD_22") (pintype "input"))
      (node (ref "IC3") (pin "8") (pinfunction "RD_8") (pintype "input"))
      (node (ref "IC6") (pin "13") (pinfunction "~{RD}_13") (pintype "input"))
      (node (ref "SV2") (pin "34") (pinfunction "34_34") (pintype "passive"))
      (node (ref "U$1") (pin "2") (pinfunction "~{I/OW}_2") (pintype "bidirectional"))
      (node (ref "U$2") (pin "8") (pinfunction "~{RD}_8") (pintype "bidirectional"))
    )
    (net (code "64") (name "IO_WR") (class "Default")
      (node (ref "CON1") (pin "35") (pinfunction "/IOWR_35") (pintype "input"))
      (node (ref "IC1") (pin "2") (pinfunction "WR_2") (pintype "input"))
      (node (ref "IC2") (pin "23") (pinfunction "WR_23") (pintype "input"))
      (node (ref "IC3") (pin "10") (pinfunction "WR_10") (pintype "input"))
      (node (ref "IC6") (pin "10") (pinfunction "~{WR}_10") (pintype "input"))
      (node (ref "SV2") (pin "35") (pinfunction "35_35") (pintype "passive"))
      (node (ref "U$1") (pin "1") (pinfunction "~{I/OR}_1") (pintype "bidirectional"))
      (node (ref "U$2") (pin "10") (pinfunction "~{WR}_10") (pintype "bidirectional"))
    )
    (net (code "65") (name "IRQ5") (class "Default")
      (node (ref "IC1") (pin "23") (pinfunction "IR5_23") (pintype "input"))
      (node (ref "SV2") (pin "50") (pinfunction "50_50") (pintype "passive"))
    )
    (net (code "66") (name "IRQ6") (class "Default")
      (node (ref "IC1") (pin "24") (pinfunction "IR6_24") (pintype "input"))
      (node (ref "SV2") (pin "51") (pinfunction "51_51") (pintype "passive"))
    )
    (net (code "67") (name "IRQ7") (class "Default")
      (node (ref "IC1") (pin "25") (pinfunction "IR7_25") (pintype "input"))
      (node (ref "SV2") (pin "52") (pinfunction "52_52") (pintype "passive"))
    )
    (net (code "68") (name "KBD_CS") (class "Default")
      (node (ref "IC3") (pin "6") (pinfunction "CS_6") (pintype "input"))
      (node (ref "IC4") (pin "10") (pinfunction "Y2_10") (pintype "output"))
    )
    (net (code "69") (name "KBD_IRQ") (class "Default")
      (node (ref "IC1") (pin "18") (pinfunction "IR0_18") (pintype "input"))
      (node (ref "IC3") (pin "35") (pinfunction "P24/OBF_35") (pintype "bidirectional"))
    )
    (net (code "70") (name "KCLK") (class "Default")
      (node (ref "C8") (pin "1") (pinfunction "1_1") (pintype "passive"))
      (node (ref "IC3") (pin "1") (pinfunction "T0_1") (pintype "input"))
      (node (ref "IC5") (pin "4") (pinfunction "O_4") (pintype "open_collector"))
      (node (ref "J1") (pin "1") (pinfunction "1_1") (pintype "bidirectional"))
      (node (ref "R7") (pin "1") (pinfunction "1_1") (pintype "passive"))
    )
    (net (code "71") (name "KDAT") (class "Default")
      (node (ref "C7") (pin "1") (pinfunction "1_1") (pintype "passive"))
      (node (ref "IC3") (pin "39") (pinfunction "T1_39") (pintype "input"))
      (node (ref "IC5") (pin "12") (pinfunction "O_12") (pintype "open_collector"))
      (node (ref "J1") (pin "2") (pinfunction "2_2") (pintype "bidirectional"))
      (node (ref "R8") (pin "1") (pinfunction "1_1") (pintype "passive"))
    )
    (net (code "72") (name "Net-(BATTERY_1-Pad+)") (class "Default")
      (node (ref "BATTERY_1") (pin "+") (pinfunction "+_+") (pintype "bidirectional"))
      (node (ref "D1") (pin "A") (pinfunction "A_A") (pintype "passive"))
    )
    (net (code "73") (name "Net-(C22-Pad+)") (class "Default")
      (node (ref "C22") (pin "+") (pinfunction "+_+") (pintype "passive"))
      (node (ref "R14") (pin "1") (pinfunction "1_1") (pintype "passive"))
      (node (ref "R15") (pin "2") (pinfunction "2_2") (pintype "passive"))
    )
    (net (code "74") (name "Net-(C22-Pad-)") (class "Default")
      (node (ref "C22") (pin "-") (pinfunction "-_-") (pintype "passive"))
      (node (ref "JP1") (pin "1") (pinfunction "1_1") (pintype "passive"))
    )
    (net (code "75") (name "Net-(CON1A-{slash}CS1)") (class "Default")
      (node (ref "CON1") (pin "32") (pinfunction "/CS1_32") (pintype "input"))
      (node (ref "R6") (pin "1") (pinfunction "1_1") (pintype "passive"))
    )
    (net (code "76") (name "Net-(CON1A-{slash}DASP)") (class "Default")
      (node (ref "CON1") (pin "45") (pinfunction "/DASP_45") (pintype "bidirectional"))
      (node (ref "LED1") (pin "K") (pinfunction "C_K") (pintype "passive"))
    )
    (net (code "77") (name "Net-(CON1A-{slash}PDIAG)") (class "Default")
      (node (ref "CON1") (pin "46") (pinfunction "/PDIAG_46") (pintype "bidirectional"))
      (node (ref "R5") (pin "1") (pinfunction "1_1") (pintype "passive"))
    )
    (net (code "78") (name "Net-(CON1A-{slash}REG)") (class "Default")
      (node (ref "CON1") (pin "44") (pinfunction "/REG_44") (pintype "input"))
      (node (ref "R4") (pin "1") (pinfunction "1_1") (pintype "passive"))
    )
    (net (code "79") (name "Net-(CON1A-{slash}WE)") (class "Default")
      (node (ref "CON1") (pin "36") (pinfunction "/WE_36") (pintype "input"))
      (node (ref "R3") (pin "1") (pinfunction "1_1") (pintype "passive"))
    )
    (net (code "80") (name "Net-(IC1A-IR3)") (class "Default")
      (node (ref "IC1") (pin "21") (pinfunction "IR3_21") (pintype "input"))
      (node (ref "IC5") (pin "6") (pinfunction "O_6") (pintype "open_collector"))
      (node (ref "R17") (pin "1") (pinfunction "1_1") (pintype "passive"))
    )
    (net (code "81") (name "Net-(IC1A-SP{slash}EN)") (class "Default")
      (node (ref "IC1") (pin "16") (pinfunction "SP/EN_16") (pintype "bidirectional"))
      (node (ref "R2") (pin "2") (pinfunction "2_2") (pintype "passive"))
    )
    (net (code "82") (name "Net-(IC2A-GATE2)") (class "Default")
      (node (ref "IC2") (pin "16") (pinfunction "GATE2_16") (pintype "input"))
      (node (ref "R11") (pin "1") (pinfunction "1_1") (pintype "passive"))
    )
    (net (code "83") (name "Net-(IC2A-OUT1)") (class "Default")
      (node (ref "IC2") (pin "13") (pinfunction "OUT1_13") (pintype "output"))
      (node (ref "R13") (pin "1") (pinfunction "1_1") (pintype "passive"))
    )
    (net (code "84") (name "Net-(IC3-P26{slash}~{DRQ})") (class "Default")
      (node (ref "IC3") (pin "37") (pinfunction "P26/~{DRQ}_37") (pintype "bidirectional"))
      (node (ref "IC5") (pin "3") (pinfunction "I_3") (pintype "input"))
    )
    (net (code "85") (name "Net-(IC3-P27{slash}~{DAK})") (class "Default")
      (node (ref "IC3") (pin "38") (pinfunction "P27/~{DAK}_38") (pintype "bidirectional"))
      (node (ref "IC5") (pin "1") (pinfunction "I_1") (pintype "input"))
    )
    (net (code "86") (name "Net-(IC3-SS)") (class "Default")
      (node (ref "IC3") (pin "5") (pinfunction "SS_5") (pintype "input"))
      (node (ref "R19") (pin "1") (pinfunction "1_1") (pintype "passive"))
    )
    (net (code "87") (name "Net-(IC3-XTAL1)") (class "Default")
      (node (ref "C9") (pin "2") (pinfunction "2_2") (pintype "passive"))
      (node (ref "IC3") (pin "2") (pinfunction "XTAL1_2") (pintype "input"))
      (node (ref "Q2") (pin "2") (pinfunction "2_2") (pintype "passive"))
    )
    (net (code "88") (name "Net-(IC3-XTAL2)") (class "Default")
      (node (ref "C11") (pin "2") (pinfunction "2_2") (pintype "passive"))
      (node (ref "IC3") (pin "3") (pinfunction "XTAL2_3") (pintype "input"))
      (node (ref "Q2") (pin "1") (pinfunction "1_1") (pintype "passive"))
    )
    (net (code "89") (name "Net-(IC5A-O)") (class "Default")
      (node (ref "IC5") (pin "13") (pinfunction "I_13") (pintype "input"))
      (node (ref "IC5") (pin "2") (pinfunction "O_2") (pintype "open_collector"))
      (node (ref "R9") (pin "2") (pinfunction "2_2") (pintype "passive"))
    )
    (net (code "90") (name "Net-(IC7A-C1+)") (class "Default")
      (node (ref "C4") (pin "2") (pinfunction "2_2") (pintype "passive"))
      (node (ref "IC7") (pin "1") (pinfunction "C1+_1") (pintype "bidirectional"))
    )
    (net (code "91") (name "Net-(IC7A-C1-)") (class "Default")
      (node (ref "C4") (pin "1") (pinfunction "1_1") (pintype "passive"))
      (node (ref "IC7") (pin "3") (pinfunction "C1-_3") (pintype "bidirectional"))
    )
    (net (code "92") (name "Net-(IC7A-C2+)") (class "Default")
      (node (ref "C5") (pin "2") (pinfunction "2_2") (pintype "passive"))
      (node (ref "IC7") (pin "4") (pinfunction "C2+_4") (pintype "bidirectional"))
    )
    (net (code "93") (name "Net-(IC7A-C2-)") (class "Default")
      (node (ref "C5") (pin "1") (pinfunction "1_1") (pintype "passive"))
      (node (ref "IC7") (pin "5") (pinfunction "C2-_5") (pintype "bidirectional"))
    )
    (net (code "94") (name "Net-(IC7A-R1IN)") (class "Default")
      (node (ref "IC7") (pin "13") (pinfunction "R1IN_13") (pintype "input"))
      (node (ref "X1") (pin "2") (pinfunction "2_2") (pintype "passive"))
    )
    (net (code "95") (name "Net-(IC7A-R2IN)") (class "Default")
      (node (ref "IC7") (pin "8") (pinfunction "R2IN_8") (pintype "input"))
      (node (ref "X1") (pin "8") (pinfunction "8_8") (pintype "passive"))
    )
    (net (code "96") (name "Net-(IC7A-T1OUT)") (class "Default")
      (node (ref "IC7") (pin "14") (pinfunction "T1OUT_14") (pintype "output"))
      (node (ref "X1") (pin "3") (pinfunction "3_3") (pintype "passive"))
    )
    (net (code "97") (name "Net-(IC7A-T2OUT)") (class "Default")
      (node (ref "IC7") (pin "7") (pinfunction "T2OUT_7") (pintype "output"))
      (node (ref "X1") (pin "7") (pinfunction "7_7") (pintype "passive"))
    )
    (net (code "98") (name "Net-(IC7A-V+)") (class "Default")
      (node (ref "C6") (pin "1") (pinfunction "1_1") (pintype "passive"))
      (node (ref "IC7") (pin "2") (pinfunction "V+_2") (pintype "bidirectional"))
    )
    (net (code "99") (name "Net-(IC7A-V-)") (class "Default")
      (node (ref "C25") (pin "1") (pinfunction "1_1") (pintype "passive"))
      (node (ref "IC7") (pin "6") (pinfunction "V-_6") (pintype "bidirectional"))
    )
    (net (code "100") (name "Net-(LED1-PadA)") (class "Default")
      (node (ref "LED1") (pin "A") (pinfunction "A_A") (pintype "passive"))
      (node (ref "R16") (pin "1") (pinfunction "1_1") (pintype "passive"))
    )
    (net (code "101") (name "Net-(T1-B)") (class "Default")
      (node (ref "R13") (pin "2") (pinfunction "2_2") (pintype "passive"))
      (node (ref "T1") (pin "1") (pinfunction "B_1") (pintype "passive"))
    )
    (net (code "102") (name "Net-(T1-C)") (class "Default")
      (node (ref "R15") (pin "1") (pinfunction "1_1") (pintype "passive"))
      (node (ref "T1") (pin "3") (pinfunction "C_3") (pintype "passive"))
    )
    (net (code "103") (name "Net-(U$1-READY)") (class "Default")
      (node (ref "R12") (pin "1") (pinfunction "1_1") (pintype "passive"))
      (node (ref "U$1") (pin "6") (pinfunction "READY_6") (pintype "bidirectional"))
    )
    (net (code "104") (name "Net-(U$2-XT)") (class "Default")
      (node (ref "C23") (pin "2") (pinfunction "2_2") (pintype "passive"))
      (node (ref "U$2") (pin "16") (pinfunction "XT_16") (pintype "bidirectional"))
      (node (ref "X2") (pin "2") (pinfunction "2_2") (pintype "passive"))
    )
    (net (code "105") (name "Net-(U$2-~{XT})") (class "Default")
      (node (ref "C20") (pin "2") (pinfunction "2_2") (pintype "passive"))
      (node (ref "U$2") (pin "17") (pinfunction "~{XT}_17") (pintype "bidirectional"))
      (node (ref "X2") (pin "1") (pinfunction "1_1") (pintype "passive"))
    )
    (net (code "106") (name "Net-(U$5-~{CLR})") (class "Default")
      (node (ref "R1") (pin "2") (pinfunction "2_2") (pintype "passive"))
      (node (ref "U$5") (pin "14") (pinfunction "~{CLR}_14") (pintype "bidirectional"))
    )
    (net (code "107") (name "OUT_1") (class "Default")
      (node (ref "SV2") (pin "3") (pinfunction "3_3") (pintype "passive"))
    )
    (net (code "108") (name "OUT_2") (class "Default")
      (node (ref "SV2") (pin "4") (pinfunction "4_4") (pintype "passive"))
    )
    (net (code "109") (name "OUT_3") (class "Default")
      (node (ref "SV2") (pin "5") (pinfunction "5_5") (pintype "passive"))
    )
    (net (code "110") (name "OUT_4") (class "Default")
      (node (ref "SV2") (pin "6") (pinfunction "6_6") (pintype "passive"))
    )
    (net (code "111") (name "RD") (class "Default")
      (node (ref "SV2") (pin "39") (pinfunction "39_39") (pintype "passive"))
      (node (ref "U$1") (pin "3") (pinfunction "~{MEMR}_3") (pintype "bidirectional"))
    )
    (net (code "112") (name "READY") (class "Default")
      (node (ref "SV2") (pin "1") (pinfunction "1_1") (pintype "passive"))
    )
    (net (code "113") (name "RESET") (class "Default")
      (node (ref "IC6") (pin "21") (pinfunction "RESET_21") (pintype "input"))
      (node (ref "SV2") (pin "31") (pinfunction "31_31") (pintype "passive"))
      (node (ref "U$1") (pin "13") (pinfunction "RESET_13") (pintype "bidirectional"))
    )
    (net (code "114") (name "RTC_IRQ") (class "Default")
      (node (ref "IC5") (pin "5") (pinfunction "I_5") (pintype "input"))
      (node (ref "R10") (pin "2") (pinfunction "2_2") (pintype "passive"))
      (node (ref "U$2") (pin "1") (pinfunction "STD.P_1") (pintype "bidirectional"))
    )
    (net (code "115") (name "RTS") (class "Default")
      (node (ref "IC6") (pin "23") (pinfunction "~{RTS}_23") (pintype "output"))
      (node (ref "IC7") (pin "10") (pinfunction "T2IN_10") (pintype "input"))
    )
    (net (code "116") (name "RXD_TTL") (class "Default")
      (node (ref "IC6") (pin "3") (pinfunction "RXD_3") (pintype "input"))
      (node (ref "IC7") (pin "12") (pinfunction "R1OUT_12") (pintype "output"))
    )
    (net (code "117") (name "TC_8257") (class "Default")
      (node (ref "SV2") (pin "54") (pinfunction "54_54") (pintype "passive"))
      (node (ref "U$1") (pin "36") (pinfunction "TC_36") (pintype "bidirectional"))
    )
    (net (code "118") (name "TIMER_CS") (class "Default")
      (node (ref "IC2") (pin "21") (pinfunction "CS_21") (pintype "input"))
      (node (ref "IC4") (pin "11") (pinfunction "Y1_11") (pintype "output"))
    )
    (net (code "119") (name "TIMER_IRQ") (class "Default")
      (node (ref "IC1") (pin "22") (pinfunction "IR4_22") (pintype "input"))
      (node (ref "IC2") (pin "10") (pinfunction "OUT0_10") (pintype "output"))
    )
    (net (code "120") (name "TXD") (class "Default")
      (node (ref "IC6") (pin "19") (pinfunction "TXD_19") (pintype "output"))
      (node (ref "IC7") (pin "11") (pinfunction "T1IN_11") (pintype "input"))
    )
    (net (code "121") (name "UART_BAUD") (class "Default")
      (node (ref "IC2") (pin "17") (pinfunction "OUT2_17") (pintype "output"))
      (node (ref "IC6") (pin "25") (pinfunction "~{RXC}_25") (pintype "input"))
      (node (ref "IC6") (pin "9") (pinfunction "~{TXC}_9") (pintype "input"))
    )
    (net (code "122") (name "UART_CS") (class "Default")
      (node (ref "IC4") (pin "12") (pinfunction "Y0_12") (pintype "output"))
      (node (ref "IC6") (pin "11") (pinfunction "~{CS}_11") (pintype "input"))
    )
    (net (code "123") (name "UART_RX_IRQ") (class "Default")
      (node (ref "IC1") (pin "20") (pinfunction "IR2_20") (pintype "input"))
      (node (ref "IC6") (pin "14") (pinfunction "RXRDY_14") (pintype "output"))
    )
    (net (code "124") (name "UART_TX_IRQ") (class "Default")
      (node (ref "IC1") (pin "19") (pinfunction "IR1_19") (pintype "input"))
      (node (ref "IC6") (pin "15") (pinfunction "TXRDY_15") (pintype "output"))
    )
    (net (code "125") (name "VCC") (class "Default")
      (node (ref "C1") (pin "1") (pinfunction "1_1") (pintype "passive"))
      (node (ref "C10") (pin "1") (pinfunction "1_1") (pintype "passive"))
      (node (ref "C12") (pin "1") (pinfunction "1_1") (pintype "passive"))
      (node (ref "C14") (pin "1") (pinfunction "1_1") (pintype "passive"))
      (node (ref "C15") (pin "1") (pinfunction "1_1") (pintype "passive"))
      (node (ref "C16") (pin "1") (pinfunction "1_1") (pintype "passive"))
      (node (ref "C17") (pin "1") (pinfunction "1_1") (pintype "passive"))
      (node (ref "C19") (pin "1") (pinfunction "1_1") (pintype "passive"))
      (node (ref "C2") (pin "1") (pinfunction "1_1") (pintype "passive"))
      (node (ref "C21") (pin "+") (pinfunction "+_+") (pintype "passive"))
      (node (ref "C24") (pin "+") (pinfunction "+_+") (pintype "passive"))
      (node (ref "C26") (pin "1") (pinfunction "1_1") (pintype "passive"))
      (node (ref "C3") (pin "1") (pinfunction "1_1") (pintype "passive"))
      (node (ref "C6") (pin "2") (pinfunction "2_2") (pintype "passive"))
      (node (ref "CON1") (pin "13") (pinfunction "VCC2_13") (pintype "power_in"))
      (node (ref "CON1") (pin "38") (pinfunction "VCC1_38") (pintype "power_in"))
      (node (ref "D2") (pin "A") (pinfunction "A_A") (pintype "passive"))
      (node (ref "IC1") (pin "28") (pinfunction "VCC_28") (pintype "power_in"))
      (node (ref "IC2") (pin "24") (pinfunction "VCC_24") (pintype "power_in"))
      (node (ref "IC3") (pin "25") (pinfunction "PROG_25") (pintype "bidirectional"))
      (node (ref "IC3") (pin "26") (pinfunction "VDD_26") (pintype "power_in"))
      (node (ref "IC3") (pin "40") (pinfunction "VCC_40") (pintype "power_in"))
      (node (ref "IC4") (pin "16") (pinfunction "VCC_16") (pintype "power_in"))
      (node (ref "IC5") (pin "14") (pinfunction "VCC_14") (pintype "power_in"))
      (node (ref "IC6") (pin "26") (pinfunction "VCC_26") (pintype "power_in"))
      (node (ref "IC7") (pin "16") (pinfunction "VCC_16") (pintype "power_in"))
      (node (ref "J1") (pin "5") (pinfunction "5_5") (pintype "bidirectional"))
      (node (ref "JP3") (pin "1") (pinfunction "1_1") (pintype "passive"))
      (node (ref "R1") (pin "1") (pinfunction "1_1") (pintype "passive"))
      (node (ref "R10") (pin "1") (pinfunction "1_1") (pintype "passive"))
      (node (ref "R11") (pin "2") (pinfunction "2_2") (pintype "passive"))
      (node (ref "R12") (pin "2") (pinfunction "2_2") (pintype "passive"))
      (node (ref "R14") (pin "2") (pinfunction "2_2") (pintype "passive"))
      (node (ref "R16") (pin "2") (pinfunction "2_2") (pintype "passive"))
      (node (ref "R17") (pin "2") (pinfunction "2_2") (pintype "passive"))
      (node (ref "R19") (pin "2") (pinfunction "2_2") (pintype "passive"))
      (node (ref "R2") (pin "1") (pinfunction "1_1") (pintype "passive"))
      (node (ref "R3") (pin "2") (pinfunction "2_2") (pintype "passive"))
      (node (ref "R4") (pin "2") (pinfunction "2_2") (pintype "passive"))
      (node (ref "R5") (pin "2") (pinfunction "2_2") (pintype "passive"))
      (node (ref "R6") (pin "2") (pinfunction "2_2") (pintype "passive"))
      (node (ref "R7") (pin "2") (pinfunction "2_2") (pintype "passive"))
      (node (ref "R8") (pin "2") (pinfunction "2_2") (pintype "passive"))
      (node (ref "R9") (pin "1") (pinfunction "1_1") (pintype "passive"))
      (node (ref "U$1") (pin "31") (pinfunction "VCC_31") (pintype "bidirectional"))
      (node (ref "U$2") (pin "15") (pinfunction "CS1_15") (pintype "bidirectional"))
      (node (ref "U$2") (pin "3") (pinfunction "ALE_3") (pintype "bidirectional"))
      (node (ref "U$5") (pin "24") (pinfunction "VCC_24") (pintype "bidirectional"))
    )
    (net (code "126") (name "VPA") (class "Default")
      (node (ref "C13") (pin "2") (pinfunction "2_2") (pintype "passive"))
      (node (ref "C18") (pin "+") (pinfunction "+_+") (pintype "passive"))
      (node (ref "D1") (pin "C") (pinfunction "C_C") (pintype "passive"))
      (node (ref "D2") (pin "C") (pinfunction "C_C") (pintype "passive"))
      (node (ref "U$2") (pin "18") (pinfunction "VDD_18") (pintype "bidirectional"))
    )
    (net (code "127") (name "WR") (class "Default")
      (node (ref "SV2") (pin "40") (pinfunction "40_40") (pintype "passive"))
      (node (ref "U$1") (pin "4") (pinfunction "~{MEMW}_4") (pintype "bidirectional"))
    )
    (net (code "128") (name "unconnected-(CON1A-D08-Pad47)") (class "Default")
      (node (ref "CON1") (pin "47") (pinfunction "D08_47") (pintype "bidirectional"))
    )
    (net (code "129") (name "unconnected-(CON1A-D09-Pad48)") (class "Default")
      (node (ref "CON1") (pin "48") (pinfunction "D09_48") (pintype "bidirectional"))
    )
    (net (code "130") (name "unconnected-(CON1A-D10-Pad49)") (class "Default")
      (node (ref "CON1") (pin "49") (pinfunction "D10_49") (pintype "bidirectional"))
    )
    (net (code "131") (name "unconnected-(CON1A-D11-Pad27)") (class "Default")
      (node (ref "CON1") (pin "27") (pinfunction "D11_27") (pintype "bidirectional"))
    )
    (net (code "132") (name "unconnected-(CON1A-D12-Pad28)") (class "Default")
      (node (ref "CON1") (pin "28") (pinfunction "D12_28") (pintype "bidirectional"))
    )
    (net (code "133") (name "unconnected-(CON1A-D13-Pad29)") (class "Default")
      (node (ref "CON1") (pin "29") (pinfunction "D13_29") (pintype "bidirectional"))
    )
    (net (code "134") (name "unconnected-(CON1A-D14-Pad30)") (class "Default")
      (node (ref "CON1") (pin "30") (pinfunction "D14_30") (pintype "bidirectional"))
    )
    (net (code "135") (name "unconnected-(CON1A-D15-Pad31)") (class "Default")
      (node (ref "CON1") (pin "31") (pinfunction "D15_31") (pintype "bidirectional"))
    )
    (net (code "136") (name "unconnected-(CON1A-INTRQ-Pad37)") (class "Default")
      (node (ref "CON1") (pin "37") (pinfunction "INTRQ_37") (pintype "output"))
    )
    (net (code "137") (name "unconnected-(CON1A-IORDY-Pad42)") (class "Default")
      (node (ref "CON1") (pin "42") (pinfunction "IORDY_42") (pintype "output"))
    )
    (net (code "138") (name "unconnected-(CON1A-{slash}CD1-Pad26)") (class "Default")
      (node (ref "CON1") (pin "26") (pinfunction "/CD1_26") (pintype "output"))
    )
    (net (code "139") (name "unconnected-(CON1A-{slash}CD2-Pad25)") (class "Default")
      (node (ref "CON1") (pin "25") (pinfunction "/CD2_25") (pintype "output"))
    )
    (net (code "140") (name "unconnected-(CON1A-{slash}INPACK-Pad43)") (class "Default")
      (node (ref "CON1") (pin "43") (pinfunction "/INPACK_43") (pintype "output"))
    )
    (net (code "141") (name "unconnected-(CON1A-{slash}IOCS16-Pad24)") (class "Default")
      (node (ref "CON1") (pin "24") (pinfunction "/IOCS16_24") (pintype "output"))
    )
    (net (code "142") (name "unconnected-(CON1A-{slash}VS1-Pad33)") (class "Default")
      (node (ref "CON1") (pin "33") (pinfunction "/VS1_33") (pintype "output"))
    )
    (net (code "143") (name "unconnected-(CON1A-{slash}VS2-Pad40)") (class "Default")
      (node (ref "CON1") (pin "40") (pinfunction "/VS2_40") (pintype "output"))
    )
    (net (code "144") (name "unconnected-(IC1A-CAS0-Pad12)") (class "Default")
      (node (ref "IC1") (pin "12") (pinfunction "CAS0_12") (pintype "bidirectional"))
    )
    (net (code "145") (name "unconnected-(IC1A-CAS1-Pad13)") (class "Default")
      (node (ref "IC1") (pin "13") (pinfunction "CAS1_13") (pintype "bidirectional"))
    )
    (net (code "146") (name "unconnected-(IC1A-CAS2-Pad15)") (class "Default")
      (node (ref "IC1") (pin "15") (pinfunction "CAS2_15") (pintype "bidirectional"))
    )
    (net (code "147") (name "unconnected-(IC3-P10-Pad27)") (class "Default")
      (node (ref "IC3") (pin "27") (pinfunction "P10_27") (pintype "bidirectional"))
    )
    (net (code "148") (name "unconnected-(IC3-P11-Pad28)") (class "Default")
      (node (ref "IC3") (pin "28") (pinfunction "P11_28") (pintype "bidirectional"))
    )
    (net (code "149") (name "unconnected-(IC3-P12-Pad29)") (class "Default")
      (node (ref "IC3") (pin "29") (pinfunction "P12_29") (pintype "bidirectional"))
    )
    (net (code "150") (name "unconnected-(IC3-P13-Pad30)") (class "Default")
      (node (ref "IC3") (pin "30") (pinfunction "P13_30") (pintype "bidirectional"))
    )
    (net (code "151") (name "unconnected-(IC3-P14-Pad31)") (class "Default")
      (node (ref "IC3") (pin "31") (pinfunction "P14_31") (pintype "bidirectional"))
    )
    (net (code "152") (name "unconnected-(IC3-P15-Pad32)") (class "Default")
      (node (ref "IC3") (pin "32") (pinfunction "P15_32") (pintype "bidirectional"))
    )
    (net (code "153") (name "unconnected-(IC3-P16-Pad33)") (class "Default")
      (node (ref "IC3") (pin "33") (pinfunction "P16_33") (pintype "bidirectional"))
    )
    (net (code "154") (name "unconnected-(IC3-P17-Pad34)") (class "Default")
      (node (ref "IC3") (pin "34") (pinfunction "P17_34") (pintype "bidirectional"))
    )
    (net (code "155") (name "unconnected-(IC3-P20-Pad21)") (class "Default")
      (node (ref "IC3") (pin "21") (pinfunction "P20_21") (pintype "bidirectional"))
    )
    (net (code "156") (name "unconnected-(IC3-P21-Pad22)") (class "Default")
      (node (ref "IC3") (pin "22") (pinfunction "P21_22") (pintype "bidirectional"))
    )
    (net (code "157") (name "unconnected-(IC3-P25{slash}~{IBF}-Pad36)") (class "Default")
      (node (ref "IC3") (pin "36") (pinfunction "P25/~{IBF}_36") (pintype "bidirectional"))
    )
    (net (code "158") (name "unconnected-(IC3-SYNC-Pad11)") (class "Default")
      (node (ref "IC3") (pin "11") (pinfunction "SYNC_11") (pintype "output"))
    )
    (net (code "159") (name "unconnected-(IC4A-Y2-Pad6)") (class "Default")
      (node (ref "IC4") (pin "6") (pinfunction "Y2_6") (pintype "output"))
    )
    (net (code "160") (name "unconnected-(IC4A-Y3-Pad7)") (class "Default")
      (node (ref "IC4") (pin "7") (pinfunction "Y3_7") (pintype "output"))
    )
    (net (code "161") (name "unconnected-(IC5D-O-Pad8)") (class "Default")
      (node (ref "IC5") (pin "8") (pinfunction "O_8") (pintype "open_collector"))
    )
    (net (code "162") (name "unconnected-(IC5E-O-Pad10)") (class "Default")
      (node (ref "IC5") (pin "10") (pinfunction "O_10") (pintype "open_collector"))
    )
    (net (code "163") (name "unconnected-(IC6-SYNDET-Pad16)") (class "Default")
      (node (ref "IC6") (pin "16") (pinfunction "SYNDET_16") (pintype "bidirectional"))
    )
    (net (code "164") (name "unconnected-(IC6-TXE-Pad18)") (class "Default")
      (node (ref "IC6") (pin "18") (pinfunction "TXE_18") (pintype "output"))
    )
    (net (code "165") (name "unconnected-(IC6-~{DTR}-Pad24)") (class "Default")
      (node (ref "IC6") (pin "24") (pinfunction "~{DTR}_24") (pintype "output"))
    )
    (net (code "166") (name "unconnected-(J1-Pad3)") (class "Default")
      (node (ref "J1") (pin "3") (pinfunction "3_3") (pintype "bidirectional"))
    )
    (net (code "167") (name "unconnected-(SV2-Pad53)") (class "Default")
      (node (ref "SV2") (pin "53") (pinfunction "53_53") (pintype "passive"))
    )
    (net (code "168") (name "unconnected-(SV2-Pad55)") (class "Default")
      (node (ref "SV2") (pin "55") (pinfunction "55_55") (pintype "passive"))
    )
    (net (code "169") (name "unconnected-(SV2-Pad56)") (class "Default")
      (node (ref "SV2") (pin "56") (pinfunction "56_56") (pintype "passive"))
    )
    (net (code "170") (name "unconnected-(SV2-Pad64)") (class "Default")
      (node (ref "SV2") (pin "64") (pinfunction "64_64") (pintype "passive"))
    )
    (net (code "171") (name "unconnected-(U$1-MARK-Pad5)") (class "Default")
      (node (ref "U$1") (pin "5") (pinfunction "MARK_5") (pintype "bidirectional"))
    )
    (net (code "172") (name "unconnected-(U$5-~{INT}-Pad23)") (class "Default")
      (node (ref "U$5") (pin "23") (pinfunction "~{INT}_23") (pintype "bidirectional"))
    )
    (net (code "173") (name "unconnected-(X1-Pad1)") (class "Default")
      (node (ref "X1") (pin "1") (pinfunction "1_1") (pintype "passive"))
    )
    (net (code "174") (name "unconnected-(X1-Pad4)") (class "Default")
      (node (ref "X1") (pin "4") (pinfunction "4_4") (pintype "passive"))
    )
    (net (code "175") (name "unconnected-(X1-Pad6)") (class "Default")
      (node (ref "X1") (pin "6") (pinfunction "6_6") (pintype "passive"))
    )
    (net (code "176") (name "unconnected-(X1-Pad9)") (class "Default")
      (node (ref "X1") (pin "9") (pinfunction "9_9") (pintype "passive"))
    )
  )
)
